# CH340G_example_schematic_5V.net
KiCad netlist of a schematic drawn in EAGLE
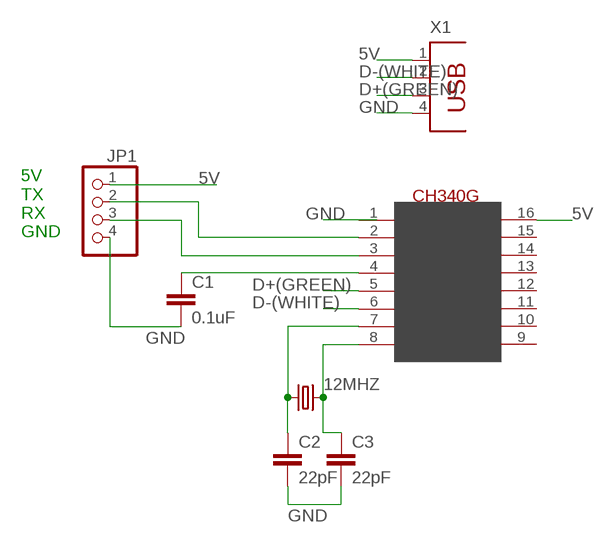
[diagram p0: schematic, sheet 1]

(export (version "E")
  (design (tool "Eeschema 10.0.6"))
  (components
    (comp (ref "12MHZ")
      (value "CRYSTALHC18U-V")
      (footprint "eagle-import:HC18U-V")
      (libsource (lib "eagle-import") (part "CRYSTALHC18U-V"))
    )
    (comp (ref "C1")
      (value "0.1uF")
      (footprint "eagle-import:C2.5-2")
      (libsource (lib "eagle-import") (part "C2.5/2"))
    )
    (comp (ref "C2")
      (value "22pF")
      (footprint "eagle-import:C2.5-2")
      (libsource (lib "eagle-import") (part "C2.5/2"))
    )
    (comp (ref "C3")
      (value "22pF")
      (footprint "eagle-import:C2.5-2")
      (libsource (lib "eagle-import") (part "C2.5/2"))
    )
    (comp (ref "JP1")
      (value "PINHD-1X4")
      (footprint "eagle-import:1X04")
      (libsource (lib "eagle-import") (part "PINHD-1X4"))
    )
    (comp (ref "U$1")
      (value "CH340G")
      (footprint "eagle-import:SOIC16")
      (libsource (lib "eagle-import") (part "CH340G"))
    )
    (comp (ref "X1")
      (value "PN61729")
      (footprint "eagle-import:PN61729")
      (libsource (lib "eagle-import") (part "PN61729"))
    )
  )
  (nets
    (net (code "1") (name "/5V") (class "Default")
      (node (ref "JP1") (pin "1") (pinfunction "1_1") (pintype "passive"))
      (node (ref "U$1") (pin "16") (pinfunction "VCC_16") (pintype "bidirectional"))
      (node (ref "X1") (pin "1") (pinfunction "1_1") (pintype "passive"))
    )
    (net (code "2") (name "/D+(GREEN)") (class "Default")
      (node (ref "U$1") (pin "5") (pinfunction "D+_5") (pintype "bidirectional"))
      (node (ref "X1") (pin "3") (pinfunction "3_3") (pintype "passive"))
    )
    (net (code "3") (name "/D-(WHITE)") (class "Default")
      (node (ref "U$1") (pin "6") (pinfunction "D-_6") (pintype "bidirectional"))
      (node (ref "X1") (pin "2") (pinfunction "2_2") (pintype "passive"))
    )
    (net (code "4") (name "/GND") (class "Default")
      (node (ref "C1") (pin "2") (pinfunction "2_2") (pintype "passive"))
      (node (ref "C2") (pin "2") (pinfunction "2_2") (pintype "passive"))
      (node (ref "C3") (pin "2") (pinfunction "2_2") (pintype "passive"))
      (node (ref "JP1") (pin "4") (pinfunction "4_4") (pintype "passive"))
      (node (ref "X1") (pin "4") (pinfunction "4_4") (pintype "passive"))
    )
    (net (code "5") (name "Net-(U$1-RX)") (class "Default")
      (node (ref "JP1") (pin "3") (pinfunction "3_3") (pintype "passive"))
      (node (ref "U$1") (pin "3") (pinfunction "RX_3") (pintype "bidirectional"))
    )
    (net (code "6") (name "Net-(U$1-TX)") (class "Default")
      (node (ref "JP1") (pin "2") (pinfunction "2_2") (pintype "passive"))
      (node (ref "U$1") (pin "2") (pinfunction "TX_2") (pintype "bidirectional"))
    )
    (net (code "7") (name "Net-(U$1-V3)") (class "Default")
      (node (ref "C1") (pin "1") (pinfunction "1_1") (pintype "passive"))
      (node (ref "U$1") (pin "4") (pinfunction "V3_4") (pintype "bidirectional"))
    )
    (net (code "8") (name "Net-(U$1-XI)") (class "Default")
      (node (ref "12MHZ") (pin "1") (pinfunction "1_1") (pintype "passive"))
      (node (ref "C2") (pin "1") (pinfunction "1_1") (pintype "passive"))
      (node (ref "U$1") (pin "7") (pinfunction "XI_7") (pintype "bidirectional"))
    )
    (net (code "9") (name "Net-(U$1-XO)") (class "Default")
      (node (ref "12MHZ") (pin "2") (pinfunction "2_2") (pintype "passive"))
      (node (ref "C3") (pin "1") (pinfunction "1_1") (pintype "passive"))
      (node (ref "U$1") (pin "8") (pinfunction "XO_8") (pintype "bidirectional"))
    )
    (net (code "10") (name "unconnected-(U$1-CTS-Pad9)") (class "Default")
      (node (ref "U$1") (pin "9") (pinfunction "CTS_9") (pintype "bidirectional"))
    )
    (net (code "11") (name "unconnected-(U$1-DCD-Pad12)") (class "Default")
      (node (ref "U$1") (pin "12") (pinfunction "DCD_12") (pintype "bidirectional"))
    )
    (net (code "12") (name "unconnected-(U$1-DSR-Pad10)") (class "Default")
      (node (ref "U$1") (pin "10") (pinfunction "DSR_10") (pintype "bidirectional"))
    )
    (net (code "13") (name "unconnected-(U$1-DTR-Pad13)") (class "Default")
      (node (ref "U$1") (pin "13") (pinfunction "DTR_13") (pintype "bidirectional"))
    )
    (net (code "14") (name "unconnected-(U$1-GND-Pad1)") (class "Default")
      (node (ref "U$1") (pin "1") (pinfunction "GND_1") (pintype "bidirectional"))
    )
    (net (code "15") (name "unconnected-(U$1-RI-Pad11)") (class "Default")
      (node (ref "U$1") (pin "11") (pinfunction "RI_11") (pintype "bidirectional"))
    )
    (net (code "16") (name "unconnected-(U$1-RS232-Pad15)") (class "Default")
      (node (ref "U$1") (pin "15") (pinfunction "RS232_15") (pintype "bidirectional"))
    )
    (net (code "17") (name "unconnected-(U$1-RTS-Pad14)") (class "Default")
      (node (ref "U$1") (pin "14") (pinfunction "RTS_14") (pintype "bidirectional"))
    )
  )
)
